# SCH_Xmas-tree_2025-12-16.net
KiCad netlist of a schematic drawn in EasyEDA
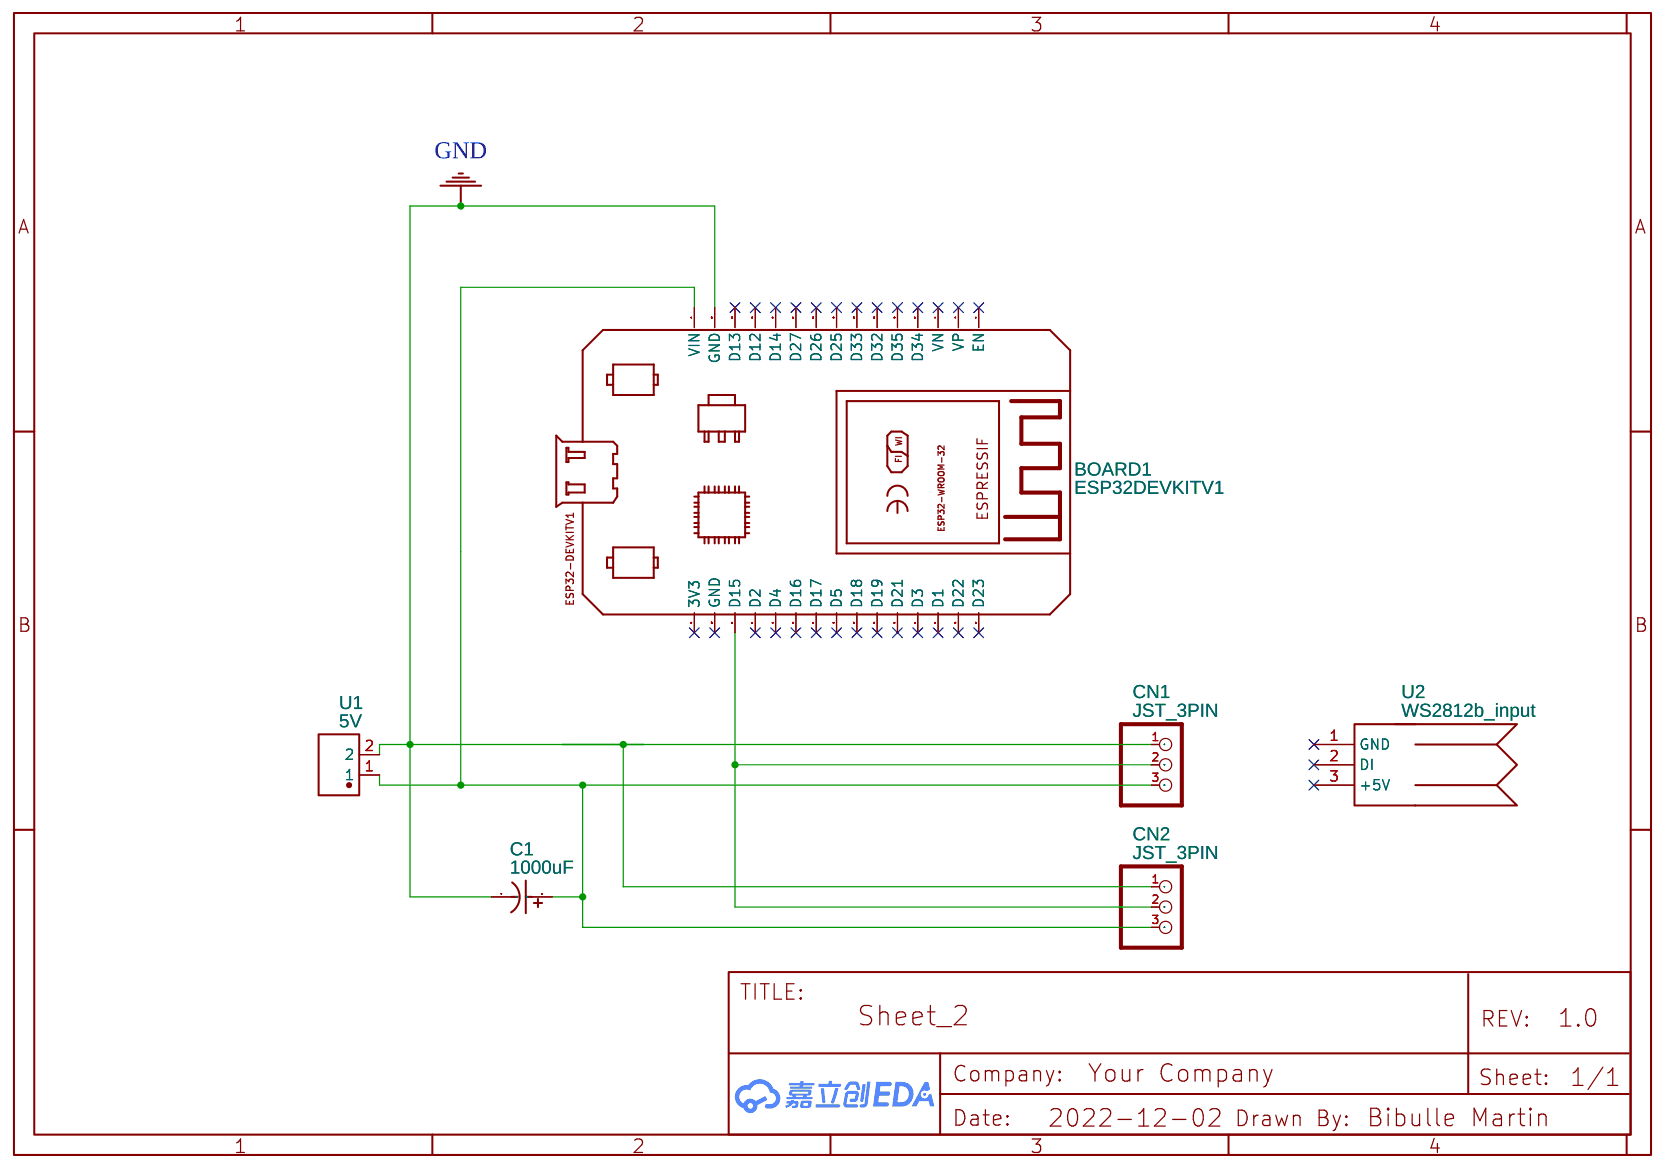
[diagram p0: Sheet_2]
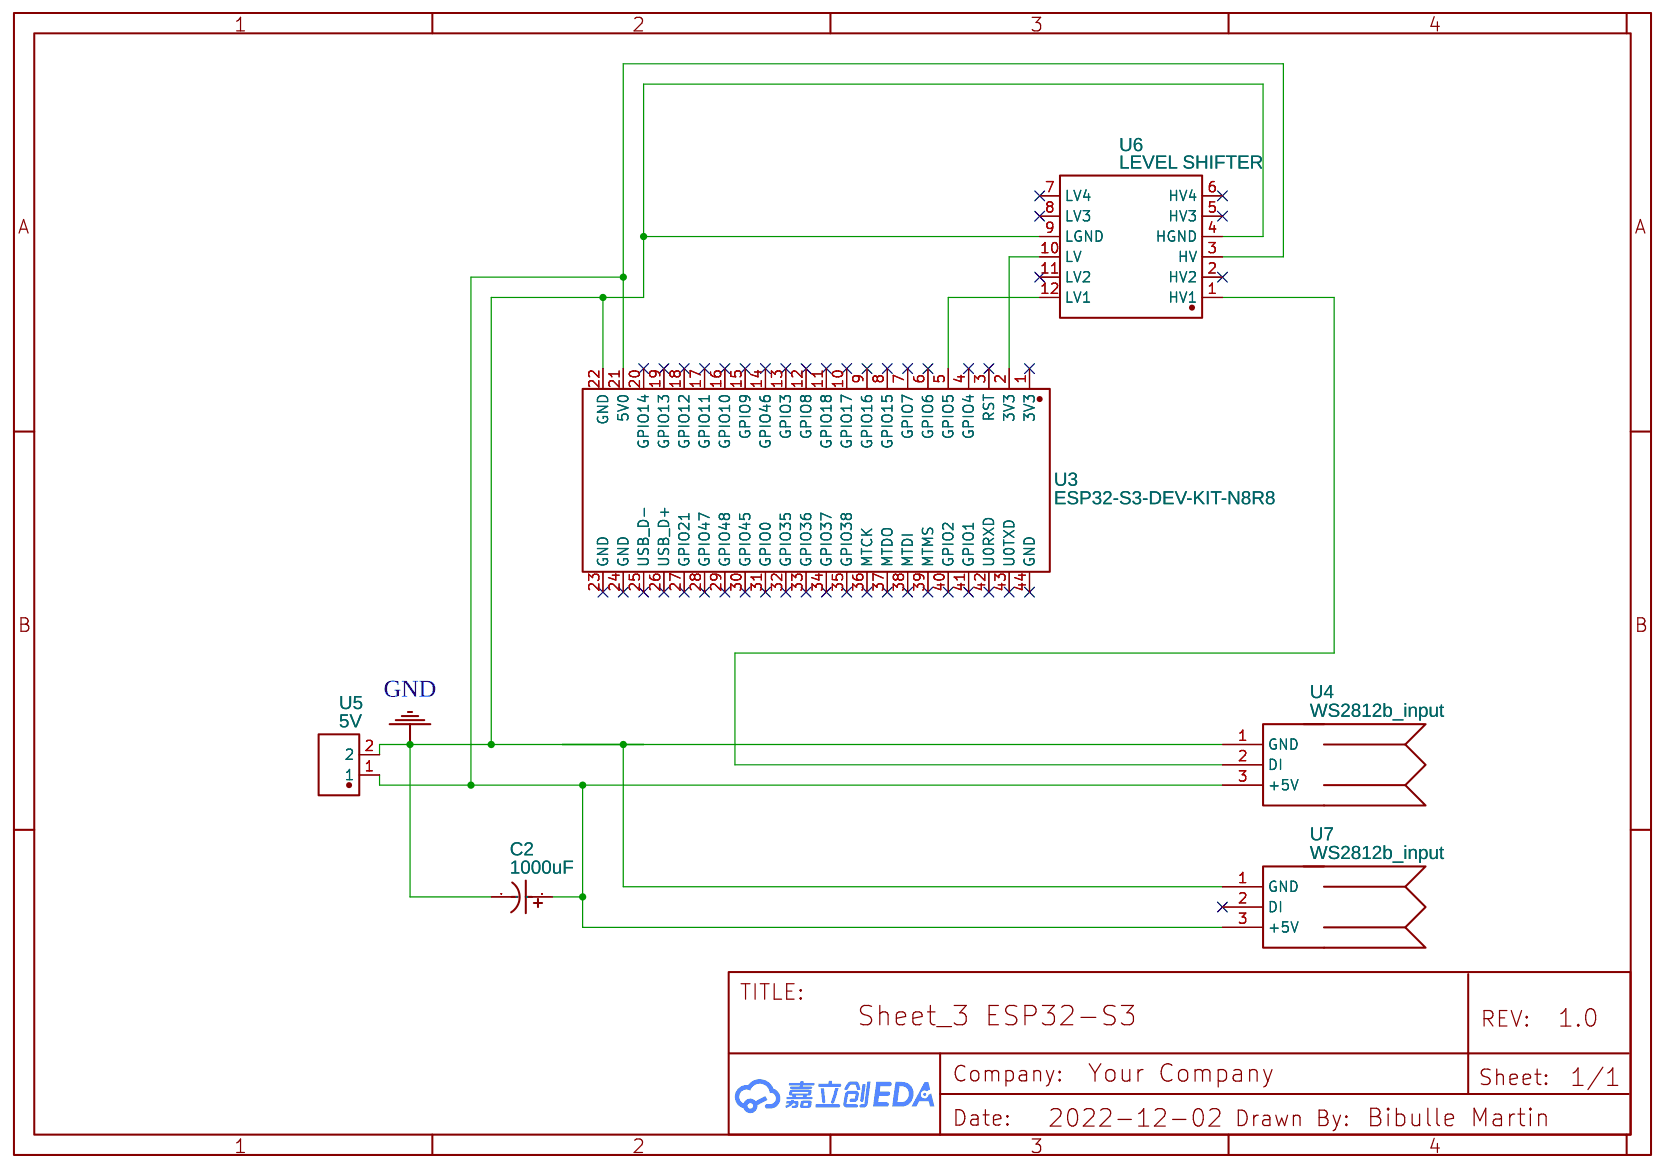
[diagram p1: Sheet_3_ESP32-S3]

(export (version "E")
  (design (tool "Eeschema 10.0.6"))
  (components
    (comp (ref "BOARD1") (value "ESP32DEVKITV1") (libsource (lib "") (part "ESP32DEVKITV1")))
    (comp (ref "C1")
      (value "1000uF")
      (fields
        (field (name "Manufacturer Part") "KM108M016F16RR0VH2FP0")
        (field (name "Manufacturer") "CX(承兴)")
      )
      (libsource (lib "") (part "1000uF 16V 8*16"))
    )
    (comp (ref "CN1") (value "JST_3PIN") (libsource (lib "") (part "JST_3PIN")))
    (comp (ref "CN2") (value "JST_3PIN") (libsource (lib "") (part "JST_3PIN")))
    (comp (ref "U1")
      (value "5V")
      (fields
        (field (name "Manufacturer Part") "DB127V-5.0-2P-GN-S")
        (field (name "Manufacturer") "DIBO(地博电气)")
      )
      (libsource (lib "") (part "DB127V-5.0-2P"))
    )
    (comp (ref "U2") (value "WS2812b_input") (libsource (lib "") (part "WS2812b_input")))
    (comp (ref "C2")
      (value "1000uF")
      (fields
        (field (name "Manufacturer Part") "KM108M016F16RR0VH2FP0")
        (field (name "Manufacturer") "CX(承兴)")
      )
      (libsource (lib "") (part "1000uF 16V 8*16"))
    )
    (comp (ref "U3") (value "ESP32-S3-DEV-KIT-N8R8") (libsource (lib "") (part "ESP32-S3-DEV-KIT-N8R8")))
    (comp (ref "U4") (value "WS2812b_input") (libsource (lib "") (part "WS2812b_input")))
    (comp (ref "U5")
      (value "5V")
      (fields
        (field (name "Manufacturer Part") "DB127V-5.0-2P-GN-S")
        (field (name "Manufacturer") "DIBO(地博电气)")
      )
      (libsource (lib "") (part "DB127V-5.0-2P"))
    )
    (comp (ref "U6") (value "LEVEL SHIFTER") (libsource (lib "") (part "ARTGEAR LEVEL SHIFTER")))
    (comp (ref "U7") (value "WS2812b_input") (libsource (lib "") (part "WS2812b_input")))
  )
  (nets
    (net (code "1") (name "GND") (class "Default")
      (node (ref "BOARD1") (pin "GND") (pinfunction "GND_GND") (pintype "bidirectional"))
      (node (ref "C1") (pin "2") (pinfunction "2_2") (pintype "input"))
      (node (ref "C2") (pin "2") (pinfunction "2_2") (pintype "input"))
      (node (ref "CN1") (pin "1") (pinfunction "1_1") (pintype "unspecified"))
      (node (ref "CN2") (pin "1") (pinfunction "1_1") (pintype "unspecified"))
      (node (ref "U1") (pin "2") (pinfunction "2_2") (pintype "unspecified"))
      (node (ref "U3") (pin "22") (pinfunction "GND_22") (pintype "unspecified"))
      (node (ref "U4") (pin "1") (pinfunction "GND_1") (pintype "unspecified"))
      (node (ref "U5") (pin "2") (pinfunction "2_2") (pintype "unspecified"))
      (node (ref "U6") (pin "4") (pinfunction "HGND_4") (pintype "passive"))
      (node (ref "U6") (pin "9") (pinfunction "LGND_9") (pintype "passive"))
      (node (ref "U7") (pin "1") (pinfunction "GND_1") (pintype "unspecified"))
    )
    (net (code "2") (name "Net-(BOARD1-PadD15)") (class "Default")
      (node (ref "BOARD1") (pin "D15") (pinfunction "D15_D15") (pintype "bidirectional"))
      (node (ref "CN1") (pin "2") (pinfunction "2_2") (pintype "unspecified"))
      (node (ref "CN2") (pin "2") (pinfunction "2_2") (pintype "unspecified"))
    )
    (net (code "3") (name "Net-(BOARD1-PadVIN)") (class "Default")
      (node (ref "BOARD1") (pin "VIN") (pinfunction "VIN_VIN") (pintype "bidirectional"))
      (node (ref "C1") (pin "1") (pinfunction "1_1") (pintype "input"))
      (node (ref "CN1") (pin "3") (pinfunction "3_3") (pintype "unspecified"))
      (node (ref "CN2") (pin "3") (pinfunction "3_3") (pintype "unspecified"))
      (node (ref "U1") (pin "1") (pinfunction "1_1") (pintype "unspecified"))
    )
    (net (code "4") (name "Net-(U3-5V0)") (class "Default")
      (node (ref "C2") (pin "1") (pinfunction "1_1") (pintype "input"))
      (node (ref "U3") (pin "21") (pinfunction "5V0_21") (pintype "unspecified"))
      (node (ref "U4") (pin "3") (pinfunction "+5V_3") (pintype "unspecified"))
      (node (ref "U5") (pin "1") (pinfunction "1_1") (pintype "unspecified"))
      (node (ref "U6") (pin "3") (pinfunction "HV_3") (pintype "passive"))
      (node (ref "U7") (pin "3") (pinfunction "+5V_3") (pintype "unspecified"))
    )
    (net (code "5") (name "Net-(U3-GPIO5)") (class "Default")
      (node (ref "U3") (pin "5") (pinfunction "GPIO5_5") (pintype "unspecified"))
      (node (ref "U6") (pin "12") (pinfunction "LV1_12") (pintype "unspecified"))
    )
    (net (code "6") (name "Net-(U4-DI)") (class "Default")
      (node (ref "U4") (pin "2") (pinfunction "DI_2") (pintype "unspecified"))
      (node (ref "U6") (pin "1") (pinfunction "HV1_1") (pintype "unspecified"))
    )
    (net (code "7") (name "Net-(U6-LV)") (class "Default")
      (node (ref "U3") (pin "2") (pinfunction "3V3_2") (pintype "unspecified"))
      (node (ref "U6") (pin "10") (pinfunction "LV_10") (pintype "passive"))
    )
    (net (code "8") (name "unconnected-(BOARD1-GND-PadGND@1)") (class "Default")
      (node (ref "BOARD1") (pin "GND@1") (pinfunction "GND_GND@1") (pintype "bidirectional+no_connect"))
    )
    (net (code "9") (name "unconnected-(BOARD1-Pad3V3)") (class "Default")
      (node (ref "BOARD1") (pin "3V3") (pinfunction "3V3_3V3") (pintype "bidirectional+no_connect"))
    )
    (net (code "10") (name "unconnected-(BOARD1-PadD1)") (class "Default")
      (node (ref "BOARD1") (pin "D1") (pinfunction "D1_D1") (pintype "bidirectional+no_connect"))
    )
    (net (code "11") (name "unconnected-(BOARD1-PadD2)") (class "Default")
      (node (ref "BOARD1") (pin "D2") (pinfunction "D2_D2") (pintype "bidirectional+no_connect"))
    )
    (net (code "12") (name "unconnected-(BOARD1-PadD3)") (class "Default")
      (node (ref "BOARD1") (pin "D3") (pinfunction "D3_D3") (pintype "bidirectional+no_connect"))
    )
    (net (code "13") (name "unconnected-(BOARD1-PadD4)") (class "Default")
      (node (ref "BOARD1") (pin "D4") (pinfunction "D4_D4") (pintype "bidirectional+no_connect"))
    )
    (net (code "14") (name "unconnected-(BOARD1-PadD5)") (class "Default")
      (node (ref "BOARD1") (pin "D5") (pinfunction "D5_D5") (pintype "bidirectional+no_connect"))
    )
    (net (code "15") (name "unconnected-(BOARD1-PadD12)") (class "Default")
      (node (ref "BOARD1") (pin "D12") (pinfunction "D12_D12") (pintype "bidirectional+no_connect"))
    )
    (net (code "16") (name "unconnected-(BOARD1-PadD13)") (class "Default")
      (node (ref "BOARD1") (pin "D13") (pinfunction "D13_D13") (pintype "bidirectional+no_connect"))
    )
    (net (code "17") (name "unconnected-(BOARD1-PadD14)") (class "Default")
      (node (ref "BOARD1") (pin "D14") (pinfunction "D14_D14") (pintype "bidirectional+no_connect"))
    )
    (net (code "18") (name "unconnected-(BOARD1-PadD16)") (class "Default")
      (node (ref "BOARD1") (pin "D16") (pinfunction "D16_D16") (pintype "bidirectional+no_connect"))
    )
    (net (code "19") (name "unconnected-(BOARD1-PadD17)") (class "Default")
      (node (ref "BOARD1") (pin "D17") (pinfunction "D17_D17") (pintype "bidirectional+no_connect"))
    )
    (net (code "20") (name "unconnected-(BOARD1-PadD18)") (class "Default")
      (node (ref "BOARD1") (pin "D18") (pinfunction "D18_D18") (pintype "bidirectional+no_connect"))
    )
    (net (code "21") (name "unconnected-(BOARD1-PadD19)") (class "Default")
      (node (ref "BOARD1") (pin "D19") (pinfunction "D19_D19") (pintype "bidirectional+no_connect"))
    )
    (net (code "22") (name "unconnected-(BOARD1-PadD21)") (class "Default")
      (node (ref "BOARD1") (pin "D21") (pinfunction "D21_D21") (pintype "bidirectional+no_connect"))
    )
    (net (code "23") (name "unconnected-(BOARD1-PadD22)") (class "Default")
      (node (ref "BOARD1") (pin "D22") (pinfunction "D22_D22") (pintype "bidirectional+no_connect"))
    )
    (net (code "24") (name "unconnected-(BOARD1-PadD23)") (class "Default")
      (node (ref "BOARD1") (pin "D23") (pinfunction "D23_D23") (pintype "bidirectional+no_connect"))
    )
    (net (code "25") (name "unconnected-(BOARD1-PadD25)") (class "Default")
      (node (ref "BOARD1") (pin "D25") (pinfunction "D25_D25") (pintype "bidirectional+no_connect"))
    )
    (net (code "26") (name "unconnected-(BOARD1-PadD26)") (class "Default")
      (node (ref "BOARD1") (pin "D26") (pinfunction "D26_D26") (pintype "bidirectional+no_connect"))
    )
    (net (code "27") (name "unconnected-(BOARD1-PadD27)") (class "Default")
      (node (ref "BOARD1") (pin "D27") (pinfunction "D27_D27") (pintype "bidirectional+no_connect"))
    )
    (net (code "28") (name "unconnected-(BOARD1-PadD32)") (class "Default")
      (node (ref "BOARD1") (pin "D32") (pinfunction "D32_D32") (pintype "bidirectional+no_connect"))
    )
    (net (code "29") (name "unconnected-(BOARD1-PadD33)") (class "Default")
      (node (ref "BOARD1") (pin "D33") (pinfunction "D33_D33") (pintype "bidirectional+no_connect"))
    )
    (net (code "30") (name "unconnected-(BOARD1-PadD34)") (class "Default")
      (node (ref "BOARD1") (pin "D34") (pinfunction "D34_D34") (pintype "bidirectional+no_connect"))
    )
    (net (code "31") (name "unconnected-(BOARD1-PadD35)") (class "Default")
      (node (ref "BOARD1") (pin "D35") (pinfunction "D35_D35") (pintype "bidirectional+no_connect"))
    )
    (net (code "32") (name "unconnected-(BOARD1-PadEN)") (class "Default")
      (node (ref "BOARD1") (pin "EN") (pinfunction "EN_EN") (pintype "bidirectional+no_connect"))
    )
    (net (code "33") (name "unconnected-(BOARD1-PadVN)") (class "Default")
      (node (ref "BOARD1") (pin "VN") (pinfunction "VN_VN") (pintype "bidirectional+no_connect"))
    )
    (net (code "34") (name "unconnected-(BOARD1-PadVP)") (class "Default")
      (node (ref "BOARD1") (pin "VP") (pinfunction "VP_VP") (pintype "bidirectional+no_connect"))
    )
    (net (code "35") (name "unconnected-(U2-+5V-Pad3)") (class "Default")
      (node (ref "U2") (pin "3") (pinfunction "+5V_3") (pintype "unspecified+no_connect"))
    )
    (net (code "36") (name "unconnected-(U2-DI-Pad2)") (class "Default")
      (node (ref "U2") (pin "2") (pinfunction "DI_2") (pintype "unspecified+no_connect"))
    )
    (net (code "37") (name "unconnected-(U2-GND-Pad1)") (class "Default")
      (node (ref "U2") (pin "1") (pinfunction "GND_1") (pintype "unspecified+no_connect"))
    )
    (net (code "38") (name "unconnected-(U3-3V3-Pad1)") (class "Default")
      (node (ref "U3") (pin "1") (pinfunction "3V3_1") (pintype "unspecified+no_connect"))
    )
    (net (code "39") (name "unconnected-(U3-GND-Pad23)") (class "Default")
      (node (ref "U3") (pin "23") (pinfunction "GND_23") (pintype "unspecified+no_connect"))
    )
    (net (code "40") (name "unconnected-(U3-GND-Pad24)") (class "Default")
      (node (ref "U3") (pin "24") (pinfunction "GND_24") (pintype "unspecified+no_connect"))
    )
    (net (code "41") (name "unconnected-(U3-GND-Pad44)") (class "Default")
      (node (ref "U3") (pin "44") (pinfunction "GND_44") (pintype "unspecified+no_connect"))
    )
    (net (code "42") (name "unconnected-(U3-GPIO0-Pad31)") (class "Default")
      (node (ref "U3") (pin "31") (pinfunction "GPIO0_31") (pintype "unspecified+no_connect"))
    )
    (net (code "43") (name "unconnected-(U3-GPIO1-Pad41)") (class "Default")
      (node (ref "U3") (pin "41") (pinfunction "GPIO1_41") (pintype "unspecified+no_connect"))
    )
    (net (code "44") (name "unconnected-(U3-GPIO2-Pad40)") (class "Default")
      (node (ref "U3") (pin "40") (pinfunction "GPIO2_40") (pintype "unspecified+no_connect"))
    )
    (net (code "45") (name "unconnected-(U3-GPIO3-Pad13)") (class "Default")
      (node (ref "U3") (pin "13") (pinfunction "GPIO3_13") (pintype "unspecified+no_connect"))
    )
    (net (code "46") (name "unconnected-(U3-GPIO4-Pad4)") (class "Default")
      (node (ref "U3") (pin "4") (pinfunction "GPIO4_4") (pintype "unspecified+no_connect"))
    )
    (net (code "47") (name "unconnected-(U3-GPIO6-Pad6)") (class "Default")
      (node (ref "U3") (pin "6") (pinfunction "GPIO6_6") (pintype "unspecified+no_connect"))
    )
    (net (code "48") (name "unconnected-(U3-GPIO7-Pad7)") (class "Default")
      (node (ref "U3") (pin "7") (pinfunction "GPIO7_7") (pintype "unspecified+no_connect"))
    )
    (net (code "49") (name "unconnected-(U3-GPIO8-Pad12)") (class "Default")
      (node (ref "U3") (pin "12") (pinfunction "GPIO8_12") (pintype "unspecified+no_connect"))
    )
    (net (code "50") (name "unconnected-(U3-GPIO9-Pad15)") (class "Default")
      (node (ref "U3") (pin "15") (pinfunction "GPIO9_15") (pintype "unspecified+no_connect"))
    )
    (net (code "51") (name "unconnected-(U3-GPIO10-Pad16)") (class "Default")
      (node (ref "U3") (pin "16") (pinfunction "GPIO10_16") (pintype "unspecified+no_connect"))
    )
    (net (code "52") (name "unconnected-(U3-GPIO11-Pad17)") (class "Default")
      (node (ref "U3") (pin "17") (pinfunction "GPIO11_17") (pintype "unspecified+no_connect"))
    )
    (net (code "53") (name "unconnected-(U3-GPIO12-Pad18)") (class "Default")
      (node (ref "U3") (pin "18") (pinfunction "GPIO12_18") (pintype "unspecified+no_connect"))
    )
    (net (code "54") (name "unconnected-(U3-GPIO13-Pad19)") (class "Default")
      (node (ref "U3") (pin "19") (pinfunction "GPIO13_19") (pintype "unspecified+no_connect"))
    )
    (net (code "55") (name "unconnected-(U3-GPIO14-Pad20)") (class "Default")
      (node (ref "U3") (pin "20") (pinfunction "GPIO14_20") (pintype "unspecified+no_connect"))
    )
    (net (code "56") (name "unconnected-(U3-GPIO15-Pad8)") (class "Default")
      (node (ref "U3") (pin "8") (pinfunction "GPIO15_8") (pintype "unspecified+no_connect"))
    )
    (net (code "57") (name "unconnected-(U3-GPIO16-Pad9)") (class "Default")
      (node (ref "U3") (pin "9") (pinfunction "GPIO16_9") (pintype "unspecified+no_connect"))
    )
    (net (code "58") (name "unconnected-(U3-GPIO17-Pad10)") (class "Default")
      (node (ref "U3") (pin "10") (pinfunction "GPIO17_10") (pintype "unspecified+no_connect"))
    )
    (net (code "59") (name "unconnected-(U3-GPIO18-Pad11)") (class "Default")
      (node (ref "U3") (pin "11") (pinfunction "GPIO18_11") (pintype "unspecified+no_connect"))
    )
    (net (code "60") (name "unconnected-(U3-GPIO21-Pad27)") (class "Default")
      (node (ref "U3") (pin "27") (pinfunction "GPIO21_27") (pintype "unspecified+no_connect"))
    )
    (net (code "61") (name "unconnected-(U3-GPIO35-Pad32)") (class "Default")
      (node (ref "U3") (pin "32") (pinfunction "GPIO35_32") (pintype "unspecified+no_connect"))
    )
    (net (code "62") (name "unconnected-(U3-GPIO36-Pad33)") (class "Default")
      (node (ref "U3") (pin "33") (pinfunction "GPIO36_33") (pintype "unspecified+no_connect"))
    )
    (net (code "63") (name "unconnected-(U3-GPIO37-Pad34)") (class "Default")
      (node (ref "U3") (pin "34") (pinfunction "GPIO37_34") (pintype "unspecified+no_connect"))
    )
    (net (code "64") (name "unconnected-(U3-GPIO38-Pad35)") (class "Default")
      (node (ref "U3") (pin "35") (pinfunction "GPIO38_35") (pintype "unspecified+no_connect"))
    )
    (net (code "65") (name "unconnected-(U3-GPIO45-Pad30)") (class "Default")
      (node (ref "U3") (pin "30") (pinfunction "GPIO45_30") (pintype "unspecified+no_connect"))
    )
    (net (code "66") (name "unconnected-(U3-GPIO46-Pad14)") (class "Default")
      (node (ref "U3") (pin "14") (pinfunction "GPIO46_14") (pintype "unspecified+no_connect"))
    )
    (net (code "67") (name "unconnected-(U3-GPIO47-Pad28)") (class "Default")
      (node (ref "U3") (pin "28") (pinfunction "GPIO47_28") (pintype "unspecified+no_connect"))
    )
    (net (code "68") (name "unconnected-(U3-GPIO48-Pad29)") (class "Default")
      (node (ref "U3") (pin "29") (pinfunction "GPIO48_29") (pintype "unspecified+no_connect"))
    )
    (net (code "69") (name "unconnected-(U3-MTCK-Pad36)") (class "Default")
      (node (ref "U3") (pin "36") (pinfunction "MTCK_36") (pintype "unspecified+no_connect"))
    )
    (net (code "70") (name "unconnected-(U3-MTDI-Pad38)") (class "Default")
      (node (ref "U3") (pin "38") (pinfunction "MTDI_38") (pintype "unspecified+no_connect"))
    )
    (net (code "71") (name "unconnected-(U3-MTDO-Pad37)") (class "Default")
      (node (ref "U3") (pin "37") (pinfunction "MTDO_37") (pintype "unspecified+no_connect"))
    )
    (net (code "72") (name "unconnected-(U3-MTMS-Pad39)") (class "Default")
      (node (ref "U3") (pin "39") (pinfunction "MTMS_39") (pintype "unspecified+no_connect"))
    )
    (net (code "73") (name "unconnected-(U3-RST-Pad3)") (class "Default")
      (node (ref "U3") (pin "3") (pinfunction "RST_3") (pintype "unspecified+no_connect"))
    )
    (net (code "74") (name "unconnected-(U3-U0RXD-Pad42)") (class "Default")
      (node (ref "U3") (pin "42") (pinfunction "U0RXD_42") (pintype "unspecified+no_connect"))
    )
    (net (code "75") (name "unconnected-(U3-U0TXD-Pad43)") (class "Default")
      (node (ref "U3") (pin "43") (pinfunction "U0TXD_43") (pintype "unspecified+no_connect"))
    )
    (net (code "76") (name "unconnected-(U3-USB_D+-Pad26)") (class "Default")
      (node (ref "U3") (pin "26") (pinfunction "USB_D+_26") (pintype "unspecified+no_connect"))
    )
    (net (code "77") (name "unconnected-(U3-USB_D--Pad25)") (class "Default")
      (node (ref "U3") (pin "25") (pinfunction "USB_D-_25") (pintype "unspecified+no_connect"))
    )
    (net (code "78") (name "unconnected-(U6-HV2-Pad2)") (class "Default")
      (node (ref "U6") (pin "2") (pinfunction "HV2_2") (pintype "unspecified+no_connect"))
    )
    (net (code "79") (name "unconnected-(U6-HV3-Pad5)") (class "Default")
      (node (ref "U6") (pin "5") (pinfunction "HV3_5") (pintype "unspecified+no_connect"))
    )
    (net (code "80") (name "unconnected-(U6-HV4-Pad6)") (class "Default")
      (node (ref "U6") (pin "6") (pinfunction "HV4_6") (pintype "unspecified+no_connect"))
    )
    (net (code "81") (name "unconnected-(U6-LV2-Pad11)") (class "Default")
      (node (ref "U6") (pin "11") (pinfunction "LV2_11") (pintype "unspecified+no_connect"))
    )
    (net (code "82") (name "unconnected-(U6-LV3-Pad8)") (class "Default")
      (node (ref "U6") (pin "8") (pinfunction "LV3_8") (pintype "unspecified+no_connect"))
    )
    (net (code "83") (name "unconnected-(U6-LV4-Pad7)") (class "Default")
      (node (ref "U6") (pin "7") (pinfunction "LV4_7") (pintype "unspecified+no_connect"))
    )
    (net (code "84") (name "unconnected-(U7-DI-Pad2)") (class "Default")
      (node (ref "U7") (pin "2") (pinfunction "DI_2") (pintype "unspecified+no_connect"))
    )
  )
)
